# SMD_R1_4.net
KiCad netlist of a schematic drawn in EAGLE
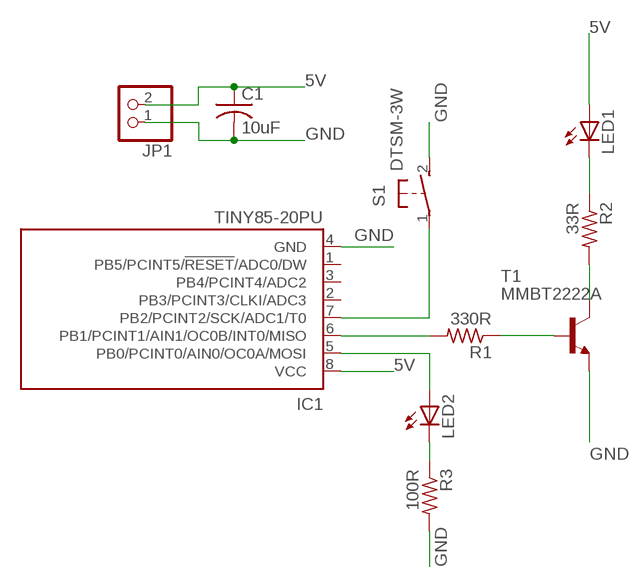
[diagram p0: schematic, sheet 1]

(export (version "E")
  (design (tool "Eeschema 10.0.6"))
  (components
    (comp (ref "C1")
      (value "10uF")
      (footprint "eagle-import:C1206K")
      (libsource (lib "eagle-import") (part "C-USC1206K"))
    )
    (comp (ref "IC1")
      (value "TINY85-20PU")
      (footprint "eagle-import:8S2")
      (fields (field (name "MPN") "ATTINY13-20SU"))
      (libsource (lib "eagle-import") (part "TINY13SU-20"))
    )
    (comp (ref "JP1")
      (value "PINHD-1X2")
      (footprint "eagle-import:1X02")
      (libsource (lib "eagle-import") (part "PINHD-1X2"))
    )
    (comp (ref "LED1")
      (value "LED5MM")
      (footprint "eagle-import:LED5MM")
      (libsource (lib "eagle-import") (part "LED5MM"))
    )
    (comp (ref "LED2")
      (value "LEDSML1206")
      (footprint "eagle-import:SML1206")
      (libsource (lib "eagle-import") (part "LEDSML1206"))
    )
    (comp (ref "R1")
      (value "330R")
      (footprint "eagle-import:R1206W")
      (libsource (lib "eagle-import") (part "R-US_R1206W"))
    )
    (comp (ref "R2")
      (value "33R")
      (footprint "eagle-import:R1206W")
      (libsource (lib "eagle-import") (part "R-US_R1206W"))
    )
    (comp (ref "R3")
      (value "100R")
      (footprint "eagle-import:R1206W")
      (libsource (lib "eagle-import") (part "R-US_R1206W"))
    )
    (comp (ref "S1")
      (value "DTSM-3W")
      (footprint "eagle-import:DTSM-3W")
      (libsource (lib "eagle-import") (part "DTSM-3W"))
    )
    (comp (ref "T1")
      (value "MMBT2222A")
      (footprint "eagle-import:SOT23-BEC")
      (libsource (lib "eagle-import") (part "-NPN-SOT23-BECMMBT2222ALT1"))
    )
  )
  (nets
    (net (code "1") (name "/5V") (class "Default")
      (node (ref "C1") (pin "1") (pinfunction "1_1") (pintype "passive"))
      (node (ref "IC1") (pin "8") (pinfunction "VCC_8") (pintype "power_in"))
      (node (ref "JP1") (pin "2") (pinfunction "2_2") (pintype "passive"))
      (node (ref "LED1") (pin "A") (pinfunction "A_A") (pintype "passive"))
    )
    (net (code "2") (name "/GND") (class "Default")
      (node (ref "C1") (pin "2") (pinfunction "2_2") (pintype "passive"))
      (node (ref "IC1") (pin "4") (pinfunction "GND_4") (pintype "power_in"))
      (node (ref "JP1") (pin "1") (pinfunction "1_1") (pintype "passive"))
      (node (ref "R3") (pin "2") (pinfunction "2_2") (pintype "passive"))
      (node (ref "S1") (pin "2") (pinfunction "2_2") (pintype "passive"))
      (node (ref "T1") (pin "E") (pinfunction "E_E") (pintype "passive"))
    )
    (net (code "3") (name "Net-(IC1-PB0{slash}PCINT0{slash}AIN0{slash}OC0A{slash}MOSI)") (class "Default")
      (node (ref "IC1") (pin "5") (pinfunction "PB0/PCINT0/AIN0/OC0A/MOSI_5") (pintype "bidirectional"))
      (node (ref "LED2") (pin "A") (pinfunction "A_A") (pintype "passive"))
    )
    (net (code "4") (name "Net-(IC1-PB1{slash}PCINT1{slash}AIN1{slash}OC0B{slash}INT0{slash}MISO)") (class "Default")
      (node (ref "IC1") (pin "6") (pinfunction "PB1/PCINT1/AIN1/OC0B/INT0/MISO_6") (pintype "bidirectional"))
      (node (ref "R1") (pin "2") (pinfunction "2_2") (pintype "passive"))
    )
    (net (code "5") (name "Net-(IC1-PB2{slash}PCINT2{slash}SCK{slash}ADC1{slash}T0)") (class "Default")
      (node (ref "IC1") (pin "7") (pinfunction "PB2/PCINT2/SCK/ADC1/T0_7") (pintype "bidirectional"))
      (node (ref "S1") (pin "1") (pinfunction "1_1") (pintype "passive"))
    )
    (net (code "6") (name "Net-(LED1-C)") (class "Default")
      (node (ref "LED1") (pin "K") (pinfunction "C_K") (pintype "passive"))
      (node (ref "R2") (pin "1") (pinfunction "1_1") (pintype "passive"))
    )
    (net (code "7") (name "Net-(LED2-PadC)") (class "Default")
      (node (ref "LED2") (pin "C") (pinfunction "C_C") (pintype "passive"))
      (node (ref "R3") (pin "1") (pinfunction "1_1") (pintype "passive"))
    )
    (net (code "8") (name "Net-(R1-Pad1)") (class "Default")
      (node (ref "R1") (pin "1") (pinfunction "1_1") (pintype "passive"))
      (node (ref "T1") (pin "B") (pinfunction "B_B") (pintype "passive"))
    )
    (net (code "9") (name "Net-(R2-Pad2)") (class "Default")
      (node (ref "R2") (pin "2") (pinfunction "2_2") (pintype "passive"))
      (node (ref "T1") (pin "C") (pinfunction "C_C") (pintype "passive"))
    )
    (net (code "10") (name "unconnected-(IC1-PB3{slash}PCINT3{slash}CLKI{slash}ADC3-Pad2)") (class "Default")
      (node (ref "IC1") (pin "2") (pinfunction "PB3/PCINT3/CLKI/ADC3_2") (pintype "bidirectional"))
    )
    (net (code "11") (name "unconnected-(IC1-PB4{slash}PCINT4{slash}ADC2-Pad3)") (class "Default")
      (node (ref "IC1") (pin "3") (pinfunction "PB4/PCINT4/ADC2_3") (pintype "bidirectional"))
    )
    (net (code "12") (name "unconnected-(IC1-PB5{slash}PCINT5{slash}~{RESET}{slash}ADC0{slash}DW-Pad1)") (class "Default")
      (node (ref "IC1") (pin "1") (pinfunction "PB5/PCINT5/~{RESET}/ADC0/DW_1") (pintype "bidirectional"))
    )
  )
)
